# monitoring_board.net
KiCad netlist of a schematic drawn in Altium Designer
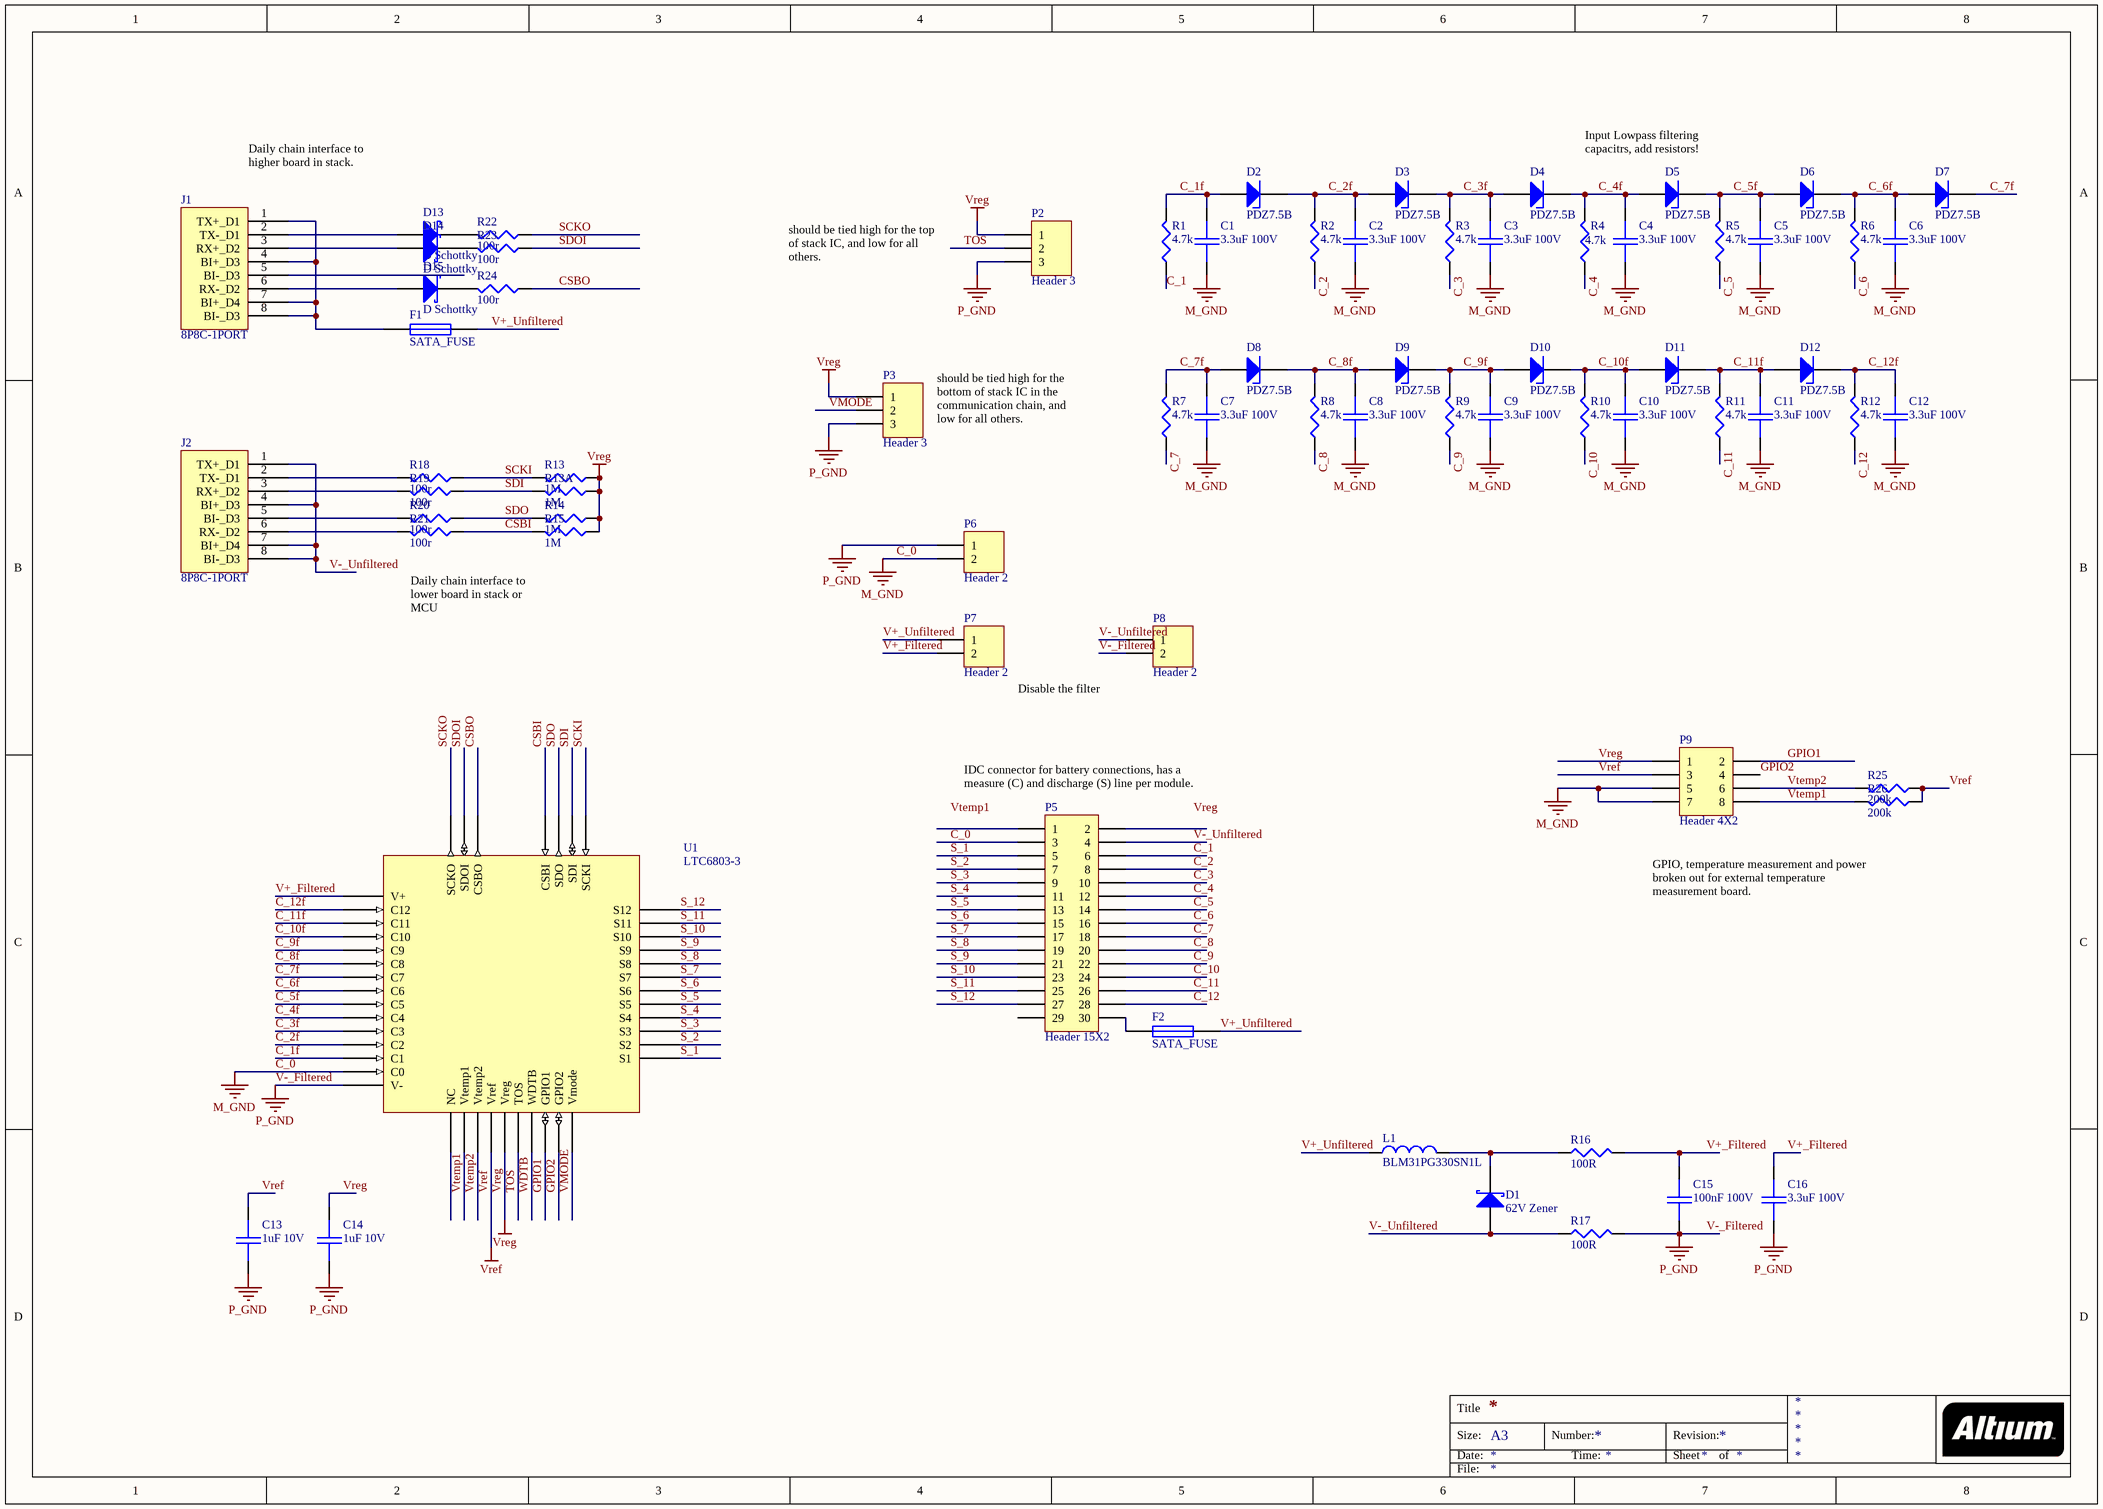
[diagram p0: monitoring_board.SchDoc]

(export (version "E")
  (design (tool "Eeschema 10.0.6"))
  (components
    (comp (ref "C1")
      (value "3.3uF 100V")
      (footprint "1206")
      (description "Capacitor")
      (libsource (lib "RCLDQ") (part "CAP"))
    )
    (comp (ref "C2")
      (value "3.3uF 100V")
      (footprint "1206")
      (description "Capacitor")
      (libsource (lib "RCLDQ") (part "CAP"))
    )
    (comp (ref "C3")
      (value "3.3uF 100V")
      (footprint "1206")
      (description "Capacitor")
      (libsource (lib "RCLDQ") (part "CAP"))
    )
    (comp (ref "C4")
      (value "3.3uF 100V")
      (footprint "1206")
      (description "Capacitor")
      (libsource (lib "RCLDQ") (part "CAP"))
    )
    (comp (ref "C5")
      (value "3.3uF 100V")
      (footprint "1206")
      (description "Capacitor")
      (libsource (lib "RCLDQ") (part "CAP"))
    )
    (comp (ref "C6")
      (value "3.3uF 100V")
      (footprint "1206")
      (description "Capacitor")
      (libsource (lib "RCLDQ") (part "CAP"))
    )
    (comp (ref "C7")
      (value "3.3uF 100V")
      (footprint "1206")
      (description "Capacitor")
      (libsource (lib "RCLDQ") (part "CAP"))
    )
    (comp (ref "C8")
      (value "3.3uF 100V")
      (footprint "1206")
      (description "Capacitor")
      (libsource (lib "RCLDQ") (part "CAP"))
    )
    (comp (ref "C9")
      (value "3.3uF 100V")
      (footprint "1206")
      (description "Capacitor")
      (libsource (lib "RCLDQ") (part "CAP"))
    )
    (comp (ref "C10")
      (value "3.3uF 100V")
      (footprint "1206")
      (description "Capacitor")
      (libsource (lib "RCLDQ") (part "CAP"))
    )
    (comp (ref "C11")
      (value "3.3uF 100V")
      (footprint "1206")
      (description "Capacitor")
      (libsource (lib "RCLDQ") (part "CAP"))
    )
    (comp (ref "C12")
      (value "3.3uF 100V")
      (footprint "1206")
      (description "Capacitor")
      (libsource (lib "RCLDQ") (part "CAP"))
    )
    (comp (ref "C13")
      (value "1uF 10V")
      (footprint "0603")
      (description "Capacitor")
      (libsource (lib "RCLDQ") (part "CAP"))
    )
    (comp (ref "C14")
      (value "1uF 10V")
      (footprint "0603")
      (description "Capacitor")
      (libsource (lib "RCLDQ") (part "CAP"))
    )
    (comp (ref "C15")
      (value "100nF 100V")
      (footprint "1206")
      (description "Capacitor")
      (libsource (lib "RCLDQ") (part "CAP"))
    )
    (comp (ref "C16")
      (value "3.3uF 100V")
      (footprint "1206")
      (description "Capacitor")
      (libsource (lib "RCLDQ") (part "CAP"))
    )
    (comp (ref "D1")
      (value "62V Zener")
      (footprint "DO-214AA")
      (description "SMBJ64CABCT-ND")
      (fields (field (name "PUBLISHER") "Altium Limited"))
      (libsource (lib "Miscellaneous Devices") (part "D Schottky"))
    )
    (comp (ref "D2")
      (value "PDZ7.5B")
      (footprint "SOD323")
      (description "Zener Diode")
      (libsource (lib "RCLDQ") (part "ZENER1"))
    )
    (comp (ref "D3")
      (value "PDZ7.5B")
      (footprint "SOD323")
      (description "Zener Diode")
      (libsource (lib "RCLDQ") (part "ZENER1"))
    )
    (comp (ref "D4")
      (value "PDZ7.5B")
      (footprint "SOD323")
      (description "Zener Diode")
      (libsource (lib "RCLDQ") (part "ZENER1"))
    )
    (comp (ref "D5")
      (value "PDZ7.5B")
      (footprint "SOD323")
      (description "Zener Diode")
      (libsource (lib "RCLDQ") (part "ZENER1"))
    )
    (comp (ref "D6")
      (value "PDZ7.5B")
      (footprint "SOD323")
      (description "Zener Diode")
      (libsource (lib "RCLDQ") (part "ZENER1"))
    )
    (comp (ref "D7")
      (value "PDZ7.5B")
      (footprint "SOD323")
      (description "Zener Diode")
      (libsource (lib "RCLDQ") (part "ZENER1"))
    )
    (comp (ref "D8")
      (value "PDZ7.5B")
      (footprint "SOD323")
      (description "Zener Diode")
      (libsource (lib "RCLDQ") (part "ZENER1"))
    )
    (comp (ref "D9")
      (value "PDZ7.5B")
      (footprint "SOD323")
      (description "Zener Diode")
      (libsource (lib "RCLDQ") (part "ZENER1"))
    )
    (comp (ref "D10")
      (value "PDZ7.5B")
      (footprint "SOD323")
      (description "Zener Diode")
      (libsource (lib "RCLDQ") (part "ZENER1"))
    )
    (comp (ref "D11")
      (value "PDZ7.5B")
      (footprint "SOD323")
      (description "Zener Diode")
      (libsource (lib "RCLDQ") (part "ZENER1"))
    )
    (comp (ref "D12")
      (value "PDZ7.5B")
      (footprint "SOD323")
      (description "Zener Diode")
      (libsource (lib "RCLDQ") (part "ZENER1"))
    )
    (comp (ref "D13")
      (value "D Schottky")
      (footprint "SMB")
      (description "Schottky Diode")
      (fields (field (name "PUBLISHER") "Altium Limited"))
      (libsource (lib "Miscellaneous Devices") (part "D Schottky"))
    )
    (comp (ref "D14")
      (value "D Schottky")
      (footprint "SMB")
      (description "Schottky Diode")
      (fields (field (name "PUBLISHER") "Altium Limited"))
      (libsource (lib "Miscellaneous Devices") (part "D Schottky"))
    )
    (comp (ref "D15")
      (value "D Schottky")
      (footprint "SMB")
      (description "Schottky Diode")
      (fields (field (name "PUBLISHER") "Altium Limited"))
      (libsource (lib "Miscellaneous Devices") (part "D Schottky"))
    )
    (comp (ref "F1")
      (value "SATA_FUSE")
      (footprint "RESC3225M_1210I")
      (description "Fuse")
      (libsource (lib "Miscellaneous") (part "FUSE"))
    )
    (comp (ref "F2")
      (value "SATA_FUSE")
      (footprint "LITTELFUSE-154")
      (description "Fuse")
      (libsource (lib "Miscellaneous") (part "FUSE"))
    )
    (comp (ref "J1")
      (value "8P8C-1PORT")
      (footprint "8P8C-1PORT")
      (libsource (lib "ethernet") (part "8P8C-1PORT"))
    )
    (comp (ref "J2")
      (value "8P8C-1PORT")
      (footprint "8P8C-1PORT")
      (libsource (lib "ethernet") (part "8P8C-1PORT"))
    )
    (comp (ref "L1")
      (value "BLM31PG330SN1L")
      (footprint "1206")
      (fields (field (name "MANUFACTURER") "Generic Components") (field (name "PUBLISHER") "Altium Limited"))
      (libsource (lib "RCLDQ") (part "INDUCTOR"))
    )
    (comp (ref "P2")
      (value "Header 3")
      (footprint "HDR1X3")
      (description "Header, 3-Pin")
      (fields (field (name "PUBLISHER") "Altium Limited"))
      (libsource (lib "Miscellaneous Connectors") (part "Header 3"))
    )
    (comp (ref "P3")
      (value "Header 3")
      (footprint "HDR1X3")
      (description "Header, 3-Pin")
      (fields (field (name "PUBLISHER") "Altium Limited"))
      (libsource (lib "Miscellaneous Connectors") (part "Header 3"))
    )
    (comp (ref "P5")
      (value "Header 15X2")
      (footprint "HDR2X15")
      (description "Header, 15-Pin, Dual row")
      (fields (field (name "PUBLISHER") "Altium Limited"))
      (libsource (lib "Miscellaneous Connectors") (part "Header 15X2"))
    )
    (comp (ref "P6")
      (value "Header 2")
      (footprint "HDR1X2")
      (description "Header, 2-Pin")
      (fields (field (name "PUBLISHER") "Altium Limited"))
      (libsource (lib "Miscellaneous Connectors") (part "Header 2"))
    )
    (comp (ref "P7")
      (value "Header 2")
      (footprint "HDR1X2")
      (description "Header, 2-Pin")
      (fields (field (name "PUBLISHER") "Altium Limited"))
      (libsource (lib "Miscellaneous Connectors") (part "Header 2"))
    )
    (comp (ref "P8")
      (value "Header 2")
      (footprint "HDR1X2")
      (description "Header, 2-Pin")
      (fields (field (name "PUBLISHER") "Altium Limited"))
      (libsource (lib "Miscellaneous Connectors") (part "Header 2"))
    )
    (comp (ref "P9")
      (value "Header 4X2")
      (footprint "HDR2X4")
      (description "Header, 4-Pin, Dual row")
      (fields (field (name "PUBLISHER") "Altium Limited"))
      (libsource (lib "Miscellaneous Connectors") (part "Header 4X2"))
    )
    (comp (ref "R1")
      (value "4.7k")
      (footprint "1206")
      (description "Resistor")
      (libsource (lib "RCLDQ") (part "RES1"))
    )
    (comp (ref "R2")
      (value "4.7k")
      (footprint "1206")
      (description "Resistor")
      (libsource (lib "RCLDQ") (part "RES1"))
    )
    (comp (ref "R3")
      (value "4.7k")
      (footprint "1206")
      (description "Resistor")
      (libsource (lib "RCLDQ") (part "RES1"))
    )
    (comp (ref "R4")
      (value "4.7k")
      (footprint "1206")
      (description "Resistor")
      (libsource (lib "RCLDQ") (part "RES1"))
    )
    (comp (ref "R5")
      (value "4.7k")
      (footprint "1206")
      (description "Resistor")
      (libsource (lib "RCLDQ") (part "RES1"))
    )
    (comp (ref "R6")
      (value "4.7k")
      (footprint "1206")
      (description "Resistor")
      (libsource (lib "RCLDQ") (part "RES1"))
    )
    (comp (ref "R7")
      (value "4.7k")
      (footprint "1206")
      (description "Resistor")
      (libsource (lib "RCLDQ") (part "RES1"))
    )
    (comp (ref "R8")
      (value "4.7k")
      (footprint "1206")
      (description "Resistor")
      (libsource (lib "RCLDQ") (part "RES1"))
    )
    (comp (ref "R9")
      (value "4.7k")
      (footprint "1206")
      (description "Resistor")
      (libsource (lib "RCLDQ") (part "RES1"))
    )
    (comp (ref "R10")
      (value "4.7k")
      (footprint "1206")
      (description "Resistor")
      (libsource (lib "RCLDQ") (part "RES1"))
    )
    (comp (ref "R11")
      (value "4.7k")
      (footprint "1206")
      (description "Resistor")
      (libsource (lib "RCLDQ") (part "RES1"))
    )
    (comp (ref "R12")
      (value "4.7k")
      (footprint "1206")
      (description "Resistor")
      (libsource (lib "RCLDQ") (part "RES1"))
    )
    (comp (ref "R13")
      (value "1M")
      (footprint "0603")
      (description "Resistor")
      (libsource (lib "RCLDQ") (part "RES1"))
    )
    (comp (ref "R13A")
      (value "1M")
      (footprint "0603")
      (description "Resistor")
      (libsource (lib "RCLDQ") (part "RES1"))
    )
    (comp (ref "R14")
      (value "1M")
      (footprint "0603")
      (description "Resistor")
      (libsource (lib "RCLDQ") (part "RES1"))
    )
    (comp (ref "R15")
      (value "1M")
      (footprint "0603")
      (description "Resistor")
      (libsource (lib "RCLDQ") (part "RES1"))
    )
    (comp (ref "R16")
      (value "100R")
      (footprint "1206")
      (description "Resistor")
      (libsource (lib "RCLDQ") (part "RES1"))
    )
    (comp (ref "R17")
      (value "100R")
      (footprint "1206")
      (description "Resistor")
      (libsource (lib "RCLDQ") (part "RES1"))
    )
    (comp (ref "R18")
      (value "100r")
      (footprint "0603")
      (description "Resistor")
      (libsource (lib "RCLDQ") (part "RES1"))
    )
    (comp (ref "R19")
      (value "100r")
      (footprint "0603")
      (description "Resistor")
      (libsource (lib "RCLDQ") (part "RES1"))
    )
    (comp (ref "R20")
      (value "100r")
      (footprint "0603")
      (description "Resistor")
      (libsource (lib "RCLDQ") (part "RES1"))
    )
    (comp (ref "R21")
      (value "100r")
      (footprint "0603")
      (description "Resistor")
      (libsource (lib "RCLDQ") (part "RES1"))
    )
    (comp (ref "R22")
      (value "100r")
      (footprint "0603")
      (description "Resistor")
      (libsource (lib "RCLDQ") (part "RES1"))
    )
    (comp (ref "R23")
      (value "100r")
      (footprint "0603")
      (description "Resistor")
      (libsource (lib "RCLDQ") (part "RES1"))
    )
    (comp (ref "R24")
      (value "100r")
      (footprint "0603")
      (description "Resistor")
      (libsource (lib "RCLDQ") (part "RES1"))
    )
    (comp (ref "R25")
      (value "200k")
      (footprint "0603")
      (description "Resistor")
      (libsource (lib "RCLDQ") (part "RES1"))
    )
    (comp (ref "R26")
      (value "200k")
      (footprint "0603")
      (description "Resistor")
      (libsource (lib "RCLDQ") (part "RES1"))
    )
    (comp (ref "U1") (value "LTC6803-3") (footprint "SOP44") (libsource (lib "BMS") (part "LTC6803-3")))
  )
  (nets
    (net (code "1") (name "/CSBI") (class "Default")
      (node (ref "R15") (pin "2") (pinfunction "2_2") (pintype "passive"))
      (node (ref "R21") (pin "1") (pinfunction "1_1") (pintype "passive"))
      (node (ref "U1") (pin "44") (pinfunction "CSBI_44") (pintype "input"))
    )
    (net (code "2") (name "/CSBO") (class "Default")
      (node (ref "R24") (pin "2") (pinfunction "2_2") (pintype "passive"))
      (node (ref "U1") (pin "1") (pinfunction "CSBO_1") (pintype "output"))
    )
    (net (code "3") (name "/C_1") (class "Default")
      (node (ref "P5") (pin "6") (pinfunction "6_6") (pintype "passive"))
      (node (ref "R1") (pin "1") (pinfunction "1_1") (pintype "passive"))
    )
    (net (code "4") (name "/C_1f") (class "Default")
      (node (ref "C1") (pin "1") (pinfunction "1_1") (pintype "passive"))
      (node (ref "D2") (pin "A") (pinfunction "A_A") (pintype "passive"))
      (node (ref "R1") (pin "2") (pinfunction "2_2") (pintype "passive"))
      (node (ref "U1") (pin "27") (pinfunction "C1_27") (pintype "input"))
    )
    (net (code "5") (name "/C_2") (class "Default")
      (node (ref "P5") (pin "8") (pinfunction "8_8") (pintype "passive"))
      (node (ref "R2") (pin "1") (pinfunction "1_1") (pintype "passive"))
    )
    (net (code "6") (name "/C_2f") (class "Default")
      (node (ref "C2") (pin "1") (pinfunction "1_1") (pintype "passive"))
      (node (ref "D2") (pin "K") (pinfunction "K_K") (pintype "passive"))
      (node (ref "D3") (pin "A") (pinfunction "A_A") (pintype "passive"))
      (node (ref "R2") (pin "2") (pinfunction "2_2") (pintype "passive"))
      (node (ref "U1") (pin "25") (pinfunction "C2_25") (pintype "input"))
    )
    (net (code "7") (name "/C_3") (class "Default")
      (node (ref "P5") (pin "10") (pinfunction "10_10") (pintype "passive"))
      (node (ref "R3") (pin "1") (pinfunction "1_1") (pintype "passive"))
    )
    (net (code "8") (name "/C_3f") (class "Default")
      (node (ref "C3") (pin "1") (pinfunction "1_1") (pintype "passive"))
      (node (ref "D3") (pin "K") (pinfunction "K_K") (pintype "passive"))
      (node (ref "D4") (pin "A") (pinfunction "A_A") (pintype "passive"))
      (node (ref "R3") (pin "2") (pinfunction "2_2") (pintype "passive"))
      (node (ref "U1") (pin "23") (pinfunction "C3_23") (pintype "input"))
    )
    (net (code "9") (name "/C_4") (class "Default")
      (node (ref "P5") (pin "12") (pinfunction "12_12") (pintype "passive"))
      (node (ref "R4") (pin "1") (pinfunction "1_1") (pintype "passive"))
    )
    (net (code "10") (name "/C_4f") (class "Default")
      (node (ref "C4") (pin "1") (pinfunction "1_1") (pintype "passive"))
      (node (ref "D4") (pin "K") (pinfunction "K_K") (pintype "passive"))
      (node (ref "D5") (pin "A") (pinfunction "A_A") (pintype "passive"))
      (node (ref "R4") (pin "2") (pinfunction "2_2") (pintype "passive"))
      (node (ref "U1") (pin "21") (pinfunction "C4_21") (pintype "input"))
    )
    (net (code "11") (name "/C_5") (class "Default")
      (node (ref "P5") (pin "14") (pinfunction "14_14") (pintype "passive"))
      (node (ref "R5") (pin "1") (pinfunction "1_1") (pintype "passive"))
    )
    (net (code "12") (name "/C_5f") (class "Default")
      (node (ref "C5") (pin "1") (pinfunction "1_1") (pintype "passive"))
      (node (ref "D5") (pin "K") (pinfunction "K_K") (pintype "passive"))
      (node (ref "D6") (pin "A") (pinfunction "A_A") (pintype "passive"))
      (node (ref "R5") (pin "2") (pinfunction "2_2") (pintype "passive"))
      (node (ref "U1") (pin "19") (pinfunction "C5_19") (pintype "input"))
    )
    (net (code "13") (name "/C_6") (class "Default")
      (node (ref "P5") (pin "16") (pinfunction "16_16") (pintype "passive"))
      (node (ref "R6") (pin "1") (pinfunction "1_1") (pintype "passive"))
    )
    (net (code "14") (name "/C_6f") (class "Default")
      (node (ref "C6") (pin "1") (pinfunction "1_1") (pintype "passive"))
      (node (ref "D6") (pin "K") (pinfunction "K_K") (pintype "passive"))
      (node (ref "D7") (pin "A") (pinfunction "A_A") (pintype "passive"))
      (node (ref "R6") (pin "2") (pinfunction "2_2") (pintype "passive"))
      (node (ref "U1") (pin "17") (pinfunction "C6_17") (pintype "input"))
    )
    (net (code "15") (name "/C_7") (class "Default")
      (node (ref "P5") (pin "18") (pinfunction "18_18") (pintype "passive"))
      (node (ref "R7") (pin "1") (pinfunction "1_1") (pintype "passive"))
    )
    (net (code "16") (name "/C_7f") (class "Default")
      (node (ref "C7") (pin "1") (pinfunction "1_1") (pintype "passive"))
      (node (ref "D7") (pin "K") (pinfunction "K_K") (pintype "passive"))
      (node (ref "D8") (pin "A") (pinfunction "A_A") (pintype "passive"))
      (node (ref "R7") (pin "2") (pinfunction "2_2") (pintype "passive"))
      (node (ref "U1") (pin "15") (pinfunction "C7_15") (pintype "input"))
    )
    (net (code "17") (name "/C_8") (class "Default")
      (node (ref "P5") (pin "20") (pinfunction "20_20") (pintype "passive"))
      (node (ref "R8") (pin "1") (pinfunction "1_1") (pintype "passive"))
    )
    (net (code "18") (name "/C_8f") (class "Default")
      (node (ref "C8") (pin "1") (pinfunction "1_1") (pintype "passive"))
      (node (ref "D8") (pin "K") (pinfunction "K_K") (pintype "passive"))
      (node (ref "D9") (pin "A") (pinfunction "A_A") (pintype "passive"))
      (node (ref "R8") (pin "2") (pinfunction "2_2") (pintype "passive"))
      (node (ref "U1") (pin "13") (pinfunction "C8_13") (pintype "input"))
    )
    (net (code "19") (name "/C_9") (class "Default")
      (node (ref "P5") (pin "22") (pinfunction "22_22") (pintype "passive"))
      (node (ref "R9") (pin "1") (pinfunction "1_1") (pintype "passive"))
    )
    (net (code "20") (name "/C_9f") (class "Default")
      (node (ref "C9") (pin "1") (pinfunction "1_1") (pintype "passive"))
      (node (ref "D10") (pin "A") (pinfunction "A_A") (pintype "passive"))
      (node (ref "D9") (pin "K") (pinfunction "K_K") (pintype "passive"))
      (node (ref "R9") (pin "2") (pinfunction "2_2") (pintype "passive"))
      (node (ref "U1") (pin "11") (pinfunction "C9_11") (pintype "input"))
    )
    (net (code "21") (name "/C_10") (class "Default")
      (node (ref "P5") (pin "24") (pinfunction "24_24") (pintype "passive"))
      (node (ref "R10") (pin "1") (pinfunction "1_1") (pintype "passive"))
    )
    (net (code "22") (name "/C_10f") (class "Default")
      (node (ref "C10") (pin "1") (pinfunction "1_1") (pintype "passive"))
      (node (ref "D10") (pin "K") (pinfunction "K_K") (pintype "passive"))
      (node (ref "D11") (pin "A") (pinfunction "A_A") (pintype "passive"))
      (node (ref "R10") (pin "2") (pinfunction "2_2") (pintype "passive"))
      (node (ref "U1") (pin "9") (pinfunction "C10_9") (pintype "input"))
    )
    (net (code "23") (name "/C_11") (class "Default")
      (node (ref "P5") (pin "26") (pinfunction "26_26") (pintype "passive"))
      (node (ref "R11") (pin "1") (pinfunction "1_1") (pintype "passive"))
    )
    (net (code "24") (name "/C_11f") (class "Default")
      (node (ref "C11") (pin "1") (pinfunction "1_1") (pintype "passive"))
      (node (ref "D11") (pin "K") (pinfunction "K_K") (pintype "passive"))
      (node (ref "D12") (pin "A") (pinfunction "A_A") (pintype "passive"))
      (node (ref "R11") (pin "2") (pinfunction "2_2") (pintype "passive"))
      (node (ref "U1") (pin "7") (pinfunction "C11_7") (pintype "input"))
    )
    (net (code "25") (name "/C_12") (class "Default")
      (node (ref "P5") (pin "28") (pinfunction "28_28") (pintype "passive"))
      (node (ref "R12") (pin "1") (pinfunction "1_1") (pintype "passive"))
    )
    (net (code "26") (name "/C_12f") (class "Default")
      (node (ref "C12") (pin "1") (pinfunction "1_1") (pintype "passive"))
      (node (ref "D12") (pin "K") (pinfunction "K_K") (pintype "passive"))
      (node (ref "R12") (pin "2") (pinfunction "2_2") (pintype "passive"))
      (node (ref "U1") (pin "5") (pinfunction "C12_5") (pintype "input"))
    )
    (net (code "27") (name "/GPIO1") (class "Default")
      (node (ref "P9") (pin "2") (pinfunction "2_2") (pintype "passive"))
      (node (ref "U1") (pin "38") (pinfunction "GPIO1_38") (pintype "bidirectional"))
    )
    (net (code "28") (name "/GPIO2") (class "Default")
      (node (ref "P9") (pin "4") (pinfunction "4_4") (pintype "passive"))
      (node (ref "U1") (pin "39") (pinfunction "GPIO2_39") (pintype "bidirectional"))
    )
    (net (code "29") (name "/SCKI") (class "Default")
      (node (ref "R13") (pin "2") (pinfunction "2_2") (pintype "passive"))
      (node (ref "R18") (pin "1") (pinfunction "1_1") (pintype "passive"))
      (node (ref "U1") (pin "41") (pinfunction "SCKI_41") (pintype "input"))
    )
    (net (code "30") (name "/SCKO") (class "Default")
      (node (ref "R22") (pin "2") (pinfunction "2_2") (pintype "passive"))
      (node (ref "U1") (pin "3") (pinfunction "SCKO_3") (pintype "output"))
    )
    (net (code "31") (name "/SDI") (class "Default")
      (node (ref "R13A") (pin "2") (pinfunction "2_2") (pintype "passive"))
      (node (ref "R19") (pin "1") (pinfunction "1_1") (pintype "passive"))
      (node (ref "U1") (pin "42") (pinfunction "SDI_42") (pintype "bidirectional"))
    )
    (net (code "32") (name "/SDO") (class "Default")
      (node (ref "R14") (pin "2") (pinfunction "2_2") (pintype "passive"))
      (node (ref "R20") (pin "1") (pinfunction "1_1") (pintype "passive"))
      (node (ref "U1") (pin "43") (pinfunction "SDO_43") (pintype "output"))
    )
    (net (code "33") (name "/SDOI") (class "Default")
      (node (ref "R23") (pin "2") (pinfunction "2_2") (pintype "passive"))
      (node (ref "U1") (pin "2") (pinfunction "SDOI_2") (pintype "bidirectional"))
    )
    (net (code "34") (name "/S_1") (class "Default")
      (node (ref "P5") (pin "5") (pinfunction "5_5") (pintype "passive"))
      (node (ref "U1") (pin "28") (pinfunction "S1_28") (pintype "passive"))
    )
    (net (code "35") (name "/S_2") (class "Default")
      (node (ref "P5") (pin "7") (pinfunction "7_7") (pintype "passive"))
      (node (ref "U1") (pin "26") (pinfunction "S2_26") (pintype "passive"))
    )
    (net (code "36") (name "/S_3") (class "Default")
      (node (ref "P5") (pin "9") (pinfunction "9_9") (pintype "passive"))
      (node (ref "U1") (pin "24") (pinfunction "S3_24") (pintype "passive"))
    )
    (net (code "37") (name "/S_4") (class "Default")
      (node (ref "P5") (pin "11") (pinfunction "11_11") (pintype "passive"))
      (node (ref "U1") (pin "22") (pinfunction "S4_22") (pintype "passive"))
    )
    (net (code "38") (name "/S_5") (class "Default")
      (node (ref "P5") (pin "13") (pinfunction "13_13") (pintype "passive"))
      (node (ref "U1") (pin "20") (pinfunction "S5_20") (pintype "passive"))
    )
    (net (code "39") (name "/S_6") (class "Default")
      (node (ref "P5") (pin "15") (pinfunction "15_15") (pintype "passive"))
      (node (ref "U1") (pin "18") (pinfunction "S6_18") (pintype "passive"))
    )
    (net (code "40") (name "/S_7") (class "Default")
      (node (ref "P5") (pin "17") (pinfunction "17_17") (pintype "passive"))
      (node (ref "U1") (pin "16") (pinfunction "S7_16") (pintype "passive"))
    )
    (net (code "41") (name "/S_8") (class "Default")
      (node (ref "P5") (pin "19") (pinfunction "19_19") (pintype "passive"))
      (node (ref "U1") (pin "14") (pinfunction "S8_14") (pintype "passive"))
    )
    (net (code "42") (name "/S_9") (class "Default")
      (node (ref "P5") (pin "21") (pinfunction "21_21") (pintype "passive"))
      (node (ref "U1") (pin "12") (pinfunction "S9_12") (pintype "passive"))
    )
    (net (code "43") (name "/S_10") (class "Default")
      (node (ref "P5") (pin "23") (pinfunction "23_23") (pintype "passive"))
      (node (ref "U1") (pin "10") (pinfunction "S10_10") (pintype "passive"))
    )
    (net (code "44") (name "/S_11") (class "Default")
      (node (ref "P5") (pin "25") (pinfunction "25_25") (pintype "passive"))
      (node (ref "U1") (pin "8") (pinfunction "S11_8") (pintype "passive"))
    )
    (net (code "45") (name "/S_12") (class "Default")
      (node (ref "P5") (pin "27") (pinfunction "27_27") (pintype "passive"))
      (node (ref "U1") (pin "6") (pinfunction "S12_6") (pintype "passive"))
    )
    (net (code "46") (name "/TOS") (class "Default")
      (node (ref "P2") (pin "2") (pinfunction "2_2") (pintype "passive"))
      (node (ref "U1") (pin "36") (pinfunction "TOS_36") (pintype "passive"))
    )
    (net (code "47") (name "/V+_Filtered") (class "Default")
      (node (ref "C15") (pin "1") (pinfunction "1_1") (pintype "passive"))
      (node (ref "C16") (pin "1") (pinfunction "1_1") (pintype "passive"))
      (node (ref "P7") (pin "2") (pinfunction "2_2") (pintype "passive"))
      (node (ref "R16") (pin "2") (pinfunction "2_2") (pintype "passive"))
      (node (ref "U1") (pin "4") (pinfunction "V+_4") (pintype "power_in"))
    )
    (net (code "48") (name "/V+_Unfiltered") (class "Default")
      (node (ref "F1") (pin "1") (pinfunction "1_1") (pintype "passive"))
      (node (ref "F2") (pin "1") (pinfunction "1_1") (pintype "passive"))
      (node (ref "L1") (pin "1") (pinfunction "1_1") (pintype "passive"))
      (node (ref "P7") (pin "1") (pinfunction "1_1") (pintype "passive"))
    )
    (net (code "49") (name "/V-_Unfiltered") (class "Default")
      (node (ref "D1") (pin "1") (pinfunction "A_1") (pintype "passive"))
      (node (ref "J2") (pin "1") (pinfunction "TX+_D1_1") (pintype "passive"))
      (node (ref "J2") (pin "4") (pinfunction "BI+_D3_4") (pintype "passive"))
      (node (ref "J2") (pin "7") (pinfunction "BI+_D4_7") (pintype "passive"))
      (node (ref "J2") (pin "8") (pinfunction "BI-_D3_8") (pintype "passive"))
      (node (ref "P5") (pin "4") (pinfunction "4_4") (pintype "passive"))
      (node (ref "P8") (pin "1") (pinfunction "1_1") (pintype "passive"))
      (node (ref "R17") (pin "1") (pinfunction "1_1") (pintype "passive"))
    )
    (net (code "50") (name "/VMODE") (class "Default")
      (node (ref "P3") (pin "2") (pinfunction "2_2") (pintype "passive"))
      (node (ref "U1") (pin "40") (pinfunction "Vmode_40") (pintype "passive"))
    )
    (net (code "51") (name "/Vtemp1") (class "Default")
      (node (ref "P9") (pin "8") (pinfunction "8_8") (pintype "passive"))
      (node (ref "R26") (pin "2") (pinfunction "2_2") (pintype "passive"))
      (node (ref "U1") (pin "32") (pinfunction "Vtemp1_32") (pintype "passive"))
    )
    (net (code "52") (name "/Vtemp2") (class "Default")
      (node (ref "P9") (pin "6") (pinfunction "6_6") (pintype "passive"))
      (node (ref "R25") (pin "2") (pinfunction "2_2") (pintype "passive"))
      (node (ref "U1") (pin "33") (pinfunction "Vtemp2_33") (pintype "passive"))
    )
    (net (code "53") (name "/WDTB") (class "Default")
      (node (ref "U1") (pin "37") (pinfunction "WDTB_37") (pintype "passive"))
    )
    (net (code "54") (name "M_GND") (class "Default")
      (node (ref "C1") (pin "2") (pinfunction "2_2") (pintype "passive"))
      (node (ref "C10") (pin "2") (pinfunction "2_2") (pintype "passive"))
      (node (ref "C11") (pin "2") (pinfunction "2_2") (pintype "passive"))
      (node (ref "C12") (pin "2") (pinfunction "2_2") (pintype "passive"))
      (node (ref "C2") (pin "2") (pinfunction "2_2") (pintype "passive"))
      (node (ref "C3") (pin "2") (pinfunction "2_2") (pintype "passive"))
      (node (ref "C4") (pin "2") (pinfunction "2_2") (pintype "passive"))
      (node (ref "C5") (pin "2") (pinfunction "2_2") (pintype "passive"))
      (node (ref "C6") (pin "2") (pinfunction "2_2") (pintype "passive"))
      (node (ref "C7") (pin "2") (pinfunction "2_2") (pintype "passive"))
      (node (ref "C8") (pin "2") (pinfunction "2_2") (pintype "passive"))
      (node (ref "C9") (pin "2") (pinfunction "2_2") (pintype "passive"))
      (node (ref "P5") (pin "3") (pinfunction "3_3") (pintype "passive"))
      (node (ref "P6") (pin "2") (pinfunction "2_2") (pintype "passive"))
      (node (ref "P9") (pin "5") (pinfunction "5_5") (pintype "passive"))
      (node (ref "P9") (pin "7") (pinfunction "7_7") (pintype "passive"))
      (node (ref "U1") (pin "29") (pinfunction "C0_29") (pintype "input"))
    )
    (net (code "55") (name "Net-(D1-K)") (class "Default")
      (node (ref "D1") (pin "2") (pinfunction "K_2") (pintype "passive"))
      (node (ref "L1") (pin "2") (pinfunction "2_2") (pintype "passive"))
      (node (ref "R16") (pin "1") (pinfunction "1_1") (pintype "passive"))
    )
    (net (code "56") (name "Net-(D13-A)") (class "Default")
      (node (ref "D13") (pin "1") (pinfunction "A_1") (pintype "passive"))
      (node (ref "J1") (pin "2") (pinfunction "TX-_D1_2") (pintype "passive"))
    )
    (net (code "57") (name "Net-(D13-K)") (class "Default")
      (node (ref "D13") (pin "2") (pinfunction "K_2") (pintype "passive"))
      (node (ref "R22") (pin "1") (pinfunction "1_1") (pintype "passive"))
    )
    (net (code "58") (name "Net-(D14-A)") (class "Default")
      (node (ref "D14") (pin "1") (pinfunction "A_1") (pintype "passive"))
      (node (ref "J1") (pin "3") (pinfunction "RX+_D2_3") (pintype "passive"))
    )
    (net (code "59") (name "Net-(D14-K)") (class "Default")
      (node (ref "D14") (pin "2") (pinfunction "K_2") (pintype "passive"))
      (node (ref "R23") (pin "1") (pinfunction "1_1") (pintype "passive"))
    )
    (net (code "60") (name "Net-(D15-A)") (class "Default")
      (node (ref "D15") (pin "1") (pinfunction "A_1") (pintype "passive"))
      (node (ref "J1") (pin "6") (pinfunction "RX-_D2_6") (pintype "passive"))
    )
    (net (code "61") (name "Net-(D15-K)") (class "Default")
      (node (ref "D15") (pin "2") (pinfunction "K_2") (pintype "passive"))
      (node (ref "R24") (pin "1") (pinfunction "1_1") (pintype "passive"))
    )
    (net (code "62") (name "Net-(F2-Pad2)") (class "Default")
      (node (ref "F2") (pin "2") (pinfunction "2_2") (pintype "passive"))
      (node (ref "P5") (pin "30") (pinfunction "30_30") (pintype "passive"))
    )
    (net (code "63") (name "Net-(J1-BI+_D3)") (class "Default")
      (node (ref "F1") (pin "2") (pinfunction "2_2") (pintype "passive"))
      (node (ref "J1") (pin "1") (pinfunction "TX+_D1_1") (pintype "passive"))
      (node (ref "J1") (pin "4") (pinfunction "BI+_D3_4") (pintype "passive"))
      (node (ref "J1") (pin "7") (pinfunction "BI+_D4_7") (pintype "passive"))
      (node (ref "J1") (pin "8") (pinfunction "BI-_D3_8") (pintype "passive"))
    )
    (net (code "64") (name "Net-(J2-BI-_D3-Pad5)") (class "Default")
      (node (ref "J2") (pin "5") (pinfunction "BI-_D3_5") (pintype "passive"))
      (node (ref "R20") (pin "2") (pinfunction "2_2") (pintype "passive"))
    )
    (net (code "65") (name "Net-(J2-RX+_D2)") (class "Default")
      (node (ref "J2") (pin "3") (pinfunction "RX+_D2_3") (pintype "passive"))
      (node (ref "R19") (pin "2") (pinfunction "2_2") (pintype "passive"))
    )
    (net (code "66") (name "Net-(J2-RX-_D2)") (class "Default")
      (node (ref "J2") (pin "6") (pinfunction "RX-_D2_6") (pintype "passive"))
      (node (ref "R21") (pin "2") (pinfunction "2_2") (pintype "passive"))
    )
    (net (code "67") (name "Net-(J2-TX-_D1)") (class "Default")
      (node (ref "J2") (pin "2") (pinfunction "TX-_D1_2") (pintype "passive"))
      (node (ref "R18") (pin "2") (pinfunction "2_2") (pintype "passive"))
    )
    (net (code "68") (name "P_GND") (class "Default")
      (node (ref "C13") (pin "2") (pinfunction "2_2") (pintype "passive"))
      (node (ref "C14") (pin "2") (pinfunction "2_2") (pintype "passive"))
      (node (ref "C15") (pin "2") (pinfunction "2_2") (pintype "passive"))
      (node (ref "C16") (pin "2") (pinfunction "2_2") (pintype "passive"))
      (node (ref "P2") (pin "3") (pinfunction "3_3") (pintype "passive"))
      (node (ref "P3") (pin "3") (pinfunction "3_3") (pintype "passive"))
      (node (ref "P6") (pin "1") (pinfunction "1_1") (pintype "passive"))
      (node (ref "P8") (pin "2") (pinfunction "2_2") (pintype "passive"))
      (node (ref "R17") (pin "2") (pinfunction "2_2") (pintype "passive"))
      (node (ref "U1") (pin "30") (pinfunction "V-_30") (pintype "power_in"))
    )
    (net (code "69") (name "Vref") (class "Default")
      (node (ref "C13") (pin "1") (pinfunction "1_1") (pintype "passive"))
      (node (ref "P9") (pin "3") (pinfunction "3_3") (pintype "passive"))
      (node (ref "R25") (pin "1") (pinfunction "1_1") (pintype "passive"))
      (node (ref "R26") (pin "1") (pinfunction "1_1") (pintype "passive"))
      (node (ref "U1") (pin "34") (pinfunction "Vref_34") (pintype "passive"))
    )
    (net (code "70") (name "Vreg") (class "Default")
      (node (ref "C14") (pin "1") (pinfunction "1_1") (pintype "passive"))
      (node (ref "P2") (pin "1") (pinfunction "1_1") (pintype "passive"))
      (node (ref "P3") (pin "1") (pinfunction "1_1") (pintype "passive"))
      (node (ref "P9") (pin "1") (pinfunction "1_1") (pintype "passive"))
      (node (ref "R13") (pin "1") (pinfunction "1_1") (pintype "passive"))
      (node (ref "R13A") (pin "1") (pinfunction "1_1") (pintype "passive"))
      (node (ref "R14") (pin "1") (pinfunction "1_1") (pintype "passive"))
      (node (ref "R15") (pin "1") (pinfunction "1_1") (pintype "passive"))
      (node (ref "U1") (pin "35") (pinfunction "Vreg_35") (pintype "passive"))
    )
    (net (code "71") (name "unconnected-(J1-BI-_D3-Pad5)") (class "Default")
      (node (ref "J1") (pin "5") (pinfunction "BI-_D3_5") (pintype "passive"))
    )
    (net (code "72") (name "unconnected-(P5-Pad1)") (class "Default")
      (node (ref "P5") (pin "1") (pinfunction "1_1") (pintype "passive"))
    )
    (net (code "73") (name "unconnected-(P5-Pad2)") (class "Default")
      (node (ref "P5") (pin "2") (pinfunction "2_2") (pintype "passive"))
    )
    (net (code "74") (name "unconnected-(P5-Pad29)") (class "Default")
      (node (ref "P5") (pin "29") (pinfunction "29_29") (pintype "passive"))
    )
    (net (code "75") (name "unconnected-(U1-NC-Pad31)") (class "Default")
      (node (ref "U1") (pin "31") (pinfunction "NC_31") (pintype "passive"))
    )
  )
)
